# QT_Backpack.net
KiCad netlist of a schematic drawn in EAGLE
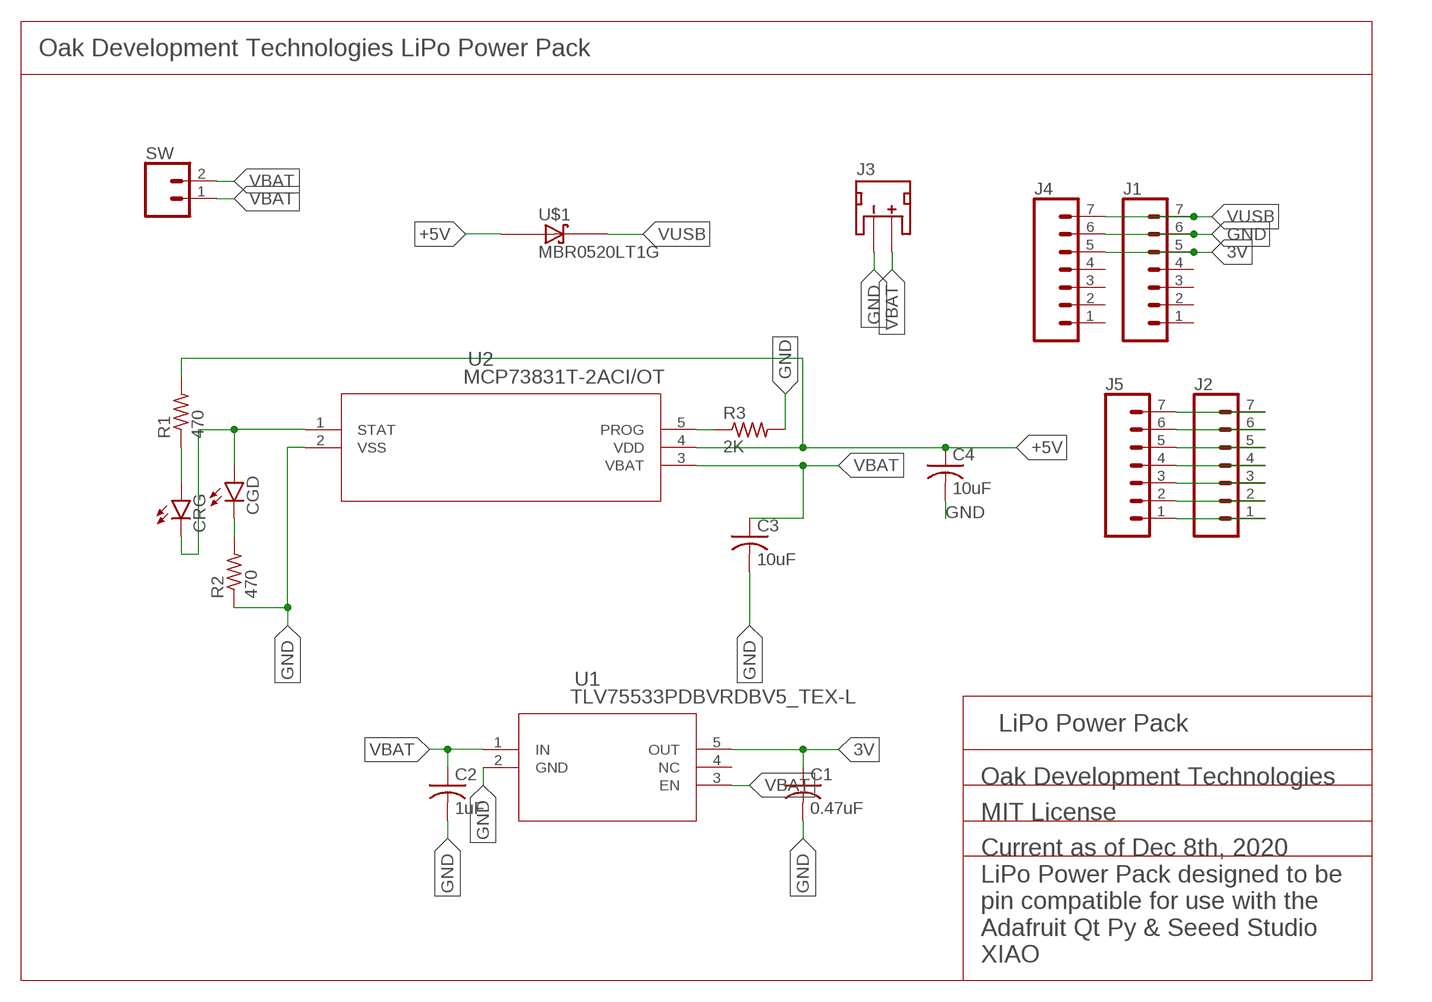
[diagram p0: schematic, sheet 1]

(export (version "E")
  (design (tool "Eeschema 10.0.6"))
  (components
    (comp (ref "C1")
      (value "0.47uF")
      (footprint "eagle-import:C0603")
      (libsource (lib "eagle-import") (part "C-USC0603"))
    )
    (comp (ref "C2")
      (value "1uF")
      (footprint "eagle-import:C0603")
      (libsource (lib "eagle-import") (part "C-USC0603"))
    )
    (comp (ref "C3")
      (value "10uF")
      (footprint "eagle-import:C0603")
      (libsource (lib "eagle-import") (part "C-USC0603"))
    )
    (comp (ref "C4")
      (value "10uF")
      (footprint "eagle-import:C0603")
      (libsource (lib "eagle-import") (part "C-USC0603"))
    )
    (comp (ref "CGD")
      (value "LEDCHIP-LED0603")
      (footprint "eagle-import:CHIP-LED0603")
      (libsource (lib "eagle-import") (part "LEDCHIP-LED0603"))
    )
    (comp (ref "CRG")
      (value "LEDCHIP-LED0603")
      (footprint "eagle-import:CHIP-LED0603")
      (libsource (lib "eagle-import") (part "LEDCHIP-LED0603"))
    )
    (comp (ref "J1")
      (value "CONN_07LONGPADS")
      (footprint "eagle-import:1X07_LONGPADS")
      (libsource (lib "eagle-import") (part "CONN_07LONGPADS"))
    )
    (comp (ref "J2")
      (value "CONN_07LONGPADS")
      (footprint "eagle-import:1X07_LONGPADS")
      (libsource (lib "eagle-import") (part "CONN_07LONGPADS"))
    )
    (comp (ref "J3")
      (value "JST_2MM_MALE")
      (footprint "eagle-import:JST-2-SMD")
      (libsource (lib "eagle-import") (part "JST_2MM_MALE"))
    )
    (comp (ref "J4")
      (value "CONN_07NO_SILK")
      (footprint "eagle-import:1X07_NO_SILK")
      (libsource (lib "eagle-import") (part "CONN_07NO_SILK"))
    )
    (comp (ref "J5")
      (value "CONN_07NO_SILK")
      (footprint "eagle-import:1X07_NO_SILK")
      (libsource (lib "eagle-import") (part "CONN_07NO_SILK"))
    )
    (comp (ref "R1")
      (value "470")
      (footprint "eagle-import:R0603")
      (libsource (lib "eagle-import") (part "R-US_R0603"))
    )
    (comp (ref "R2")
      (value "470")
      (footprint "eagle-import:R0603")
      (libsource (lib "eagle-import") (part "R-US_R0603"))
    )
    (comp (ref "R3")
      (value "2K")
      (footprint "eagle-import:R0603")
      (libsource (lib "eagle-import") (part "R-US_R0603"))
    )
    (comp (ref "SW")
      (value "CONN_02")
      (footprint "eagle-import:1X02")
      (libsource (lib "eagle-import") (part "CONN_02"))
    )
    (comp (ref "U$1")
      (value "MBR0520LT1G")
      (footprint "eagle-import:SOD3716X117(SOD-123)")
      (fields (field (name "MF") "ON Semiconductor"))
      (libsource (lib "eagle-import") (part "MBR0520LT1G"))
    )
    (comp (ref "U1")
      (value "TLV75533PDBVRDBV5_TEX-L")
      (footprint "eagle-import:DBV5_TEX-L")
      (fields
        (field (name "MANUFACTURER_PART_NUMBER") "TLV75533PDBVR")
        (field (name "COPYRIGHT") "Copyright (C) 2018 Accelerated Designs. All rights reserved")
      )
      (libsource (lib "eagle-import") (part "TLV75533PDBVRDBV5_TEX-L"))
    )
    (comp (ref "U2")
      (value "MCP73831T-2ACI/OT")
      (footprint "eagle-import:SOT-23-5_MC")
      (libsource (lib "eagle-import") (part "MCP73831T-2ACI/OT"))
    )
  )
  (nets
    (net (code "1") (name "+5V") (class "Default")
      (node (ref "C4") (pin "1") (pinfunction "1_1") (pintype "passive"))
      (node (ref "R1") (pin "2") (pinfunction "2_2") (pintype "passive"))
      (node (ref "U$1") (pin "2") (pinfunction "A_2") (pintype "passive"))
      (node (ref "U2") (pin "4") (pinfunction "VDD_4") (pintype "passive"))
    )
    (net (code "2") (name "3V") (class "Default")
      (node (ref "C1") (pin "1") (pinfunction "1_1") (pintype "passive"))
      (node (ref "J1") (pin "5") (pinfunction "5_5") (pintype "passive"))
      (node (ref "J4") (pin "5") (pinfunction "5_5") (pintype "passive"))
      (node (ref "U1") (pin "5") (pinfunction "OUT_5") (pintype "output"))
    )
    (net (code "3") (name "GND") (class "Default")
      (node (ref "C1") (pin "2") (pinfunction "2_2") (pintype "passive"))
      (node (ref "C2") (pin "2") (pinfunction "2_2") (pintype "passive"))
      (node (ref "C3") (pin "2") (pinfunction "2_2") (pintype "passive"))
      (node (ref "C4") (pin "2") (pinfunction "2_2") (pintype "passive"))
      (node (ref "J1") (pin "6") (pinfunction "6_6") (pintype "passive"))
      (node (ref "J3") (pin "1") (pinfunction "-_1") (pintype "bidirectional"))
      (node (ref "J4") (pin "6") (pinfunction "6_6") (pintype "passive"))
      (node (ref "R2") (pin "1") (pinfunction "1_1") (pintype "passive"))
      (node (ref "R3") (pin "2") (pinfunction "2_2") (pintype "passive"))
      (node (ref "U1") (pin "2") (pinfunction "GND_2") (pintype "power_in"))
      (node (ref "U2") (pin "2") (pinfunction "VSS_2") (pintype "passive"))
    )
    (net (code "4") (name "Net-(CGD-PadC)") (class "Default")
      (node (ref "CGD") (pin "C") (pinfunction "C_C") (pintype "passive"))
      (node (ref "R2") (pin "2") (pinfunction "2_2") (pintype "passive"))
    )
    (net (code "5") (name "Net-(CRG-PadA)") (class "Default")
      (node (ref "CRG") (pin "A") (pinfunction "A_A") (pintype "passive"))
      (node (ref "R1") (pin "1") (pinfunction "1_1") (pintype "passive"))
    )
    (net (code "6") (name "Net-(J2-Pad1)") (class "Default")
      (node (ref "J2") (pin "1") (pinfunction "1_1") (pintype "passive"))
      (node (ref "J5") (pin "1") (pinfunction "1_1") (pintype "passive"))
    )
    (net (code "7") (name "Net-(J2-Pad2)") (class "Default")
      (node (ref "J2") (pin "2") (pinfunction "2_2") (pintype "passive"))
      (node (ref "J5") (pin "2") (pinfunction "2_2") (pintype "passive"))
    )
    (net (code "8") (name "Net-(J2-Pad3)") (class "Default")
      (node (ref "J2") (pin "3") (pinfunction "3_3") (pintype "passive"))
      (node (ref "J5") (pin "3") (pinfunction "3_3") (pintype "passive"))
    )
    (net (code "9") (name "Net-(J2-Pad4)") (class "Default")
      (node (ref "J2") (pin "4") (pinfunction "4_4") (pintype "passive"))
      (node (ref "J5") (pin "4") (pinfunction "4_4") (pintype "passive"))
    )
    (net (code "10") (name "Net-(J2-Pad5)") (class "Default")
      (node (ref "J2") (pin "5") (pinfunction "5_5") (pintype "passive"))
      (node (ref "J5") (pin "5") (pinfunction "5_5") (pintype "passive"))
    )
    (net (code "11") (name "Net-(J2-Pad6)") (class "Default")
      (node (ref "J2") (pin "6") (pinfunction "6_6") (pintype "passive"))
      (node (ref "J5") (pin "6") (pinfunction "6_6") (pintype "passive"))
    )
    (net (code "12") (name "Net-(J2-Pad7)") (class "Default")
      (node (ref "J2") (pin "7") (pinfunction "7_7") (pintype "passive"))
      (node (ref "J5") (pin "7") (pinfunction "7_7") (pintype "passive"))
    )
    (net (code "13") (name "Net-(U2-PROG)") (class "Default")
      (node (ref "R3") (pin "1") (pinfunction "1_1") (pintype "passive"))
      (node (ref "U2") (pin "5") (pinfunction "PROG_5") (pintype "passive"))
    )
    (net (code "14") (name "Net-(U2-STAT)") (class "Default")
      (node (ref "CGD") (pin "A") (pinfunction "A_A") (pintype "passive"))
      (node (ref "CRG") (pin "C") (pinfunction "C_C") (pintype "passive"))
      (node (ref "U2") (pin "1") (pinfunction "STAT_1") (pintype "passive"))
    )
    (net (code "15") (name "VBAT") (class "Default")
      (node (ref "C2") (pin "1") (pinfunction "1_1") (pintype "passive"))
      (node (ref "C3") (pin "1") (pinfunction "1_1") (pintype "passive"))
      (node (ref "J3") (pin "2") (pinfunction "+_2") (pintype "bidirectional"))
      (node (ref "SW") (pin "1") (pinfunction "1_1") (pintype "passive"))
      (node (ref "SW") (pin "2") (pinfunction "2_2") (pintype "passive"))
      (node (ref "U1") (pin "1") (pinfunction "IN_1") (pintype "input"))
      (node (ref "U1") (pin "3") (pinfunction "EN_3") (pintype "input"))
      (node (ref "U2") (pin "3") (pinfunction "VBAT_3") (pintype "passive"))
    )
    (net (code "16") (name "VUSB") (class "Default")
      (node (ref "J1") (pin "7") (pinfunction "7_7") (pintype "passive"))
      (node (ref "J4") (pin "7") (pinfunction "7_7") (pintype "passive"))
      (node (ref "U$1") (pin "1") (pinfunction "C_1") (pintype "passive"))
    )
    (net (code "17") (name "unconnected-(J1-Pad1)") (class "Default")
      (node (ref "J1") (pin "1") (pinfunction "1_1") (pintype "passive"))
    )
    (net (code "18") (name "unconnected-(J1-Pad2)") (class "Default")
      (node (ref "J1") (pin "2") (pinfunction "2_2") (pintype "passive"))
    )
    (net (code "19") (name "unconnected-(J1-Pad3)") (class "Default")
      (node (ref "J1") (pin "3") (pinfunction "3_3") (pintype "passive"))
    )
    (net (code "20") (name "unconnected-(J1-Pad4)") (class "Default")
      (node (ref "J1") (pin "4") (pinfunction "4_4") (pintype "passive"))
    )
    (net (code "21") (name "unconnected-(J3-PAD1-PadNC1)") (class "Default")
      (node (ref "J3") (pin "NC1") (pinfunction "PAD1_NC1") (pintype "bidirectional"))
    )
    (net (code "22") (name "unconnected-(J3-PAD2-PadNC2)") (class "Default")
      (node (ref "J3") (pin "NC2") (pinfunction "PAD2_NC2") (pintype "bidirectional"))
    )
    (net (code "23") (name "unconnected-(J4-Pad1)") (class "Default")
      (node (ref "J4") (pin "1") (pinfunction "1_1") (pintype "passive"))
    )
    (net (code "24") (name "unconnected-(J4-Pad2)") (class "Default")
      (node (ref "J4") (pin "2") (pinfunction "2_2") (pintype "passive"))
    )
    (net (code "25") (name "unconnected-(J4-Pad3)") (class "Default")
      (node (ref "J4") (pin "3") (pinfunction "3_3") (pintype "passive"))
    )
    (net (code "26") (name "unconnected-(J4-Pad4)") (class "Default")
      (node (ref "J4") (pin "4") (pinfunction "4_4") (pintype "passive"))
    )
    (net (code "27") (name "unconnected-(U1-NC-Pad4)") (class "Default")
      (node (ref "U1") (pin "4") (pinfunction "NC_4") (pintype "no_connect"))
    )
  )
)
